# SDC_LATCH_LS.net
KiCad netlist of a schematic drawn in Altium Designer
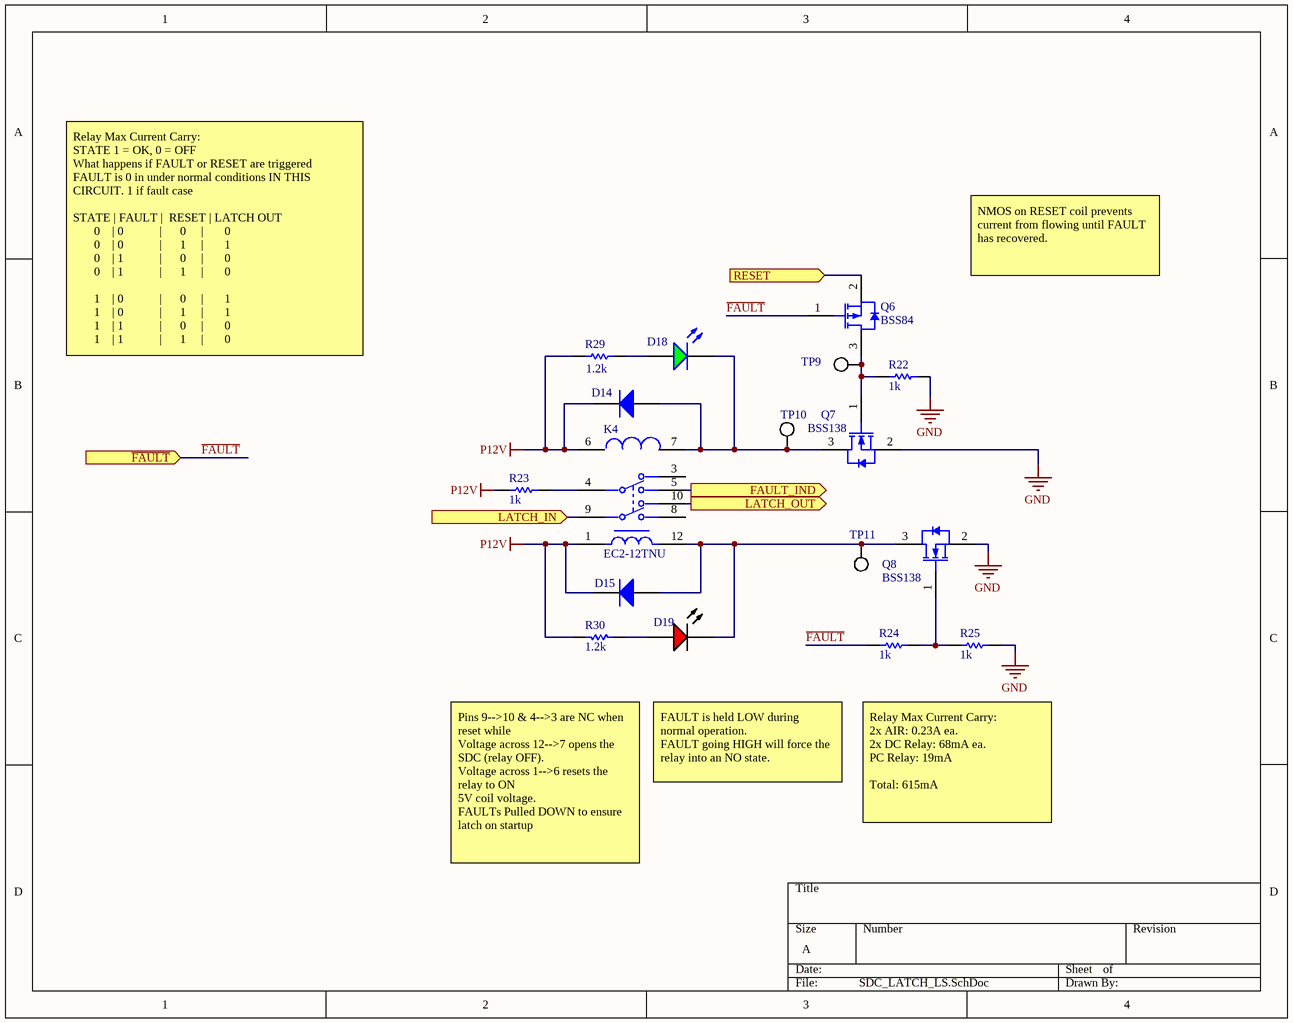
[diagram p0:  SDC_LATCH_LS.SchDoc]

(export (version "E")
  (design (tool "Eeschema 10.0.6"))
  (components
    (comp (ref "D14")
      (value "Diode 1N4148")
      (footprint "DO-35")
      (description "High Conductance Fast Diode")
      (fields (field (name "PUBLISHER") "Altium Limited"))
      (libsource (lib "Miscellaneous Devices") (part "Diode 1N4148"))
    )
    (comp (ref "D15")
      (value "Diode 1N4148")
      (footprint "DO-35")
      (description "High Conductance Fast Diode")
      (fields (field (name "PUBLISHER") "Altium Limited"))
      (libsource (lib "Miscellaneous Devices") (part "Diode 1N4148"))
    )
    (comp (ref "D18")
      (value "597-3311-407F")
      (footprint "DIAL-597-3311-407F_V")
      (description "LED Green, 75 mW, 30 mA, -30 to 85 degC, 2-Pin SMD, RoHS, Tape and Reel")
      (fields (field (name "MANUFACTURER") "Dialight"))
      (libsource (lib "Altium Content Vault") (part "LED-GREEN-AK-2"))
    )
    (comp (ref "D19")
      (value "SML-LX1206IC-TR")
      (footprint "LUMX-SML-LX1206IC_V")
      (description "LED Red, 65 mW, -40 to 85 degC, 2-Pin SMD, RoHS, Tape and Reel")
      (fields (field (name "MANUFACTURER") "Lumex"))
      (libsource (lib "Altium Content Vault") (part "LED-RED-AK-2"))
    )
    (comp (ref "K4")
      (value "EC2-12TNU")
      (footprint "FP-EC2-12TNU-MFG")
      (description "RELAY GEN PURPOSE DPDT 2A 12VDC")
      (fields
        (field (name "MANUFACTURER") "KEMET")
        (field (name "OCTOPART") "https://octopart.com/ec2-12tnu-kemet-30529205")
      )
      (libsource (lib "Altium Content Vault") (part "a00bcedd7ab582def7fa3ba9be5e2d2"))
    )
    (comp (ref "Q6")
      (value "BSS84")
      (footprint "FAIR-SOT23-3_V")
      (fields (field (name "MANUFACTURER") "Fairchild") (field (name "POWER") "360mW"))
      (libsource (lib "University of California Riverside - FSAE") (part "PEMOS-GSD-3"))
    )
    (comp (ref "Q7")
      (value "BSS138")
      (footprint "FAIR-SOT23-3_V")
      (fields (field (name "MANUFACTURER") "Fairchild") (field (name "POWER") "360mW"))
      (libsource (lib "University of California Riverside - FSAE") (part "NEMOS-GSD-3"))
    )
    (comp (ref "Q8")
      (value "BSS138")
      (footprint "FAIR-SOT23-3_V")
      (fields (field (name "MANUFACTURER") "Fairchild") (field (name "POWER") "360mW"))
      (libsource (lib "University of California Riverside - FSAE") (part "NEMOS-GSD-3"))
    )
    (comp (ref "R22")
      (value "1k")
      (footprint "RESC3116X70X50ML13T20")
      (description "Chip Resistor, 1 KOhm, +/- 1%, 0.25 W, -55 to 155 degC, 1206 (3216 Metric)")
      (fields (field (name "POWER") "250mW") (field (name "TOLERANCE") "1%"))
      (libsource (lib "University of California Riverside - FSAE") (part "RES-2"))
    )
    (comp (ref "R23")
      (value "1k")
      (footprint "RESC3116X70X50ML13T20")
      (description "Chip Resistor, 1 KOhm, +/- 1%, 0.25 W, -55 to 155 degC, 1206 (3216 Metric)")
      (fields (field (name "POWER") "250mW") (field (name "TOLERANCE") "1%"))
      (libsource (lib "University of California Riverside - FSAE") (part "RES-2"))
    )
    (comp (ref "R24")
      (value "1k")
      (footprint "RESC3116X70X50ML13T20")
      (description "Chip Resistor, 1 KOhm, +/- 1%, 0.25 W, -55 to 155 degC, 1206 (3216 Metric)")
      (fields (field (name "POWER") "250mW") (field (name "TOLERANCE") "1%"))
      (libsource (lib "University of California Riverside - FSAE") (part "RES-2"))
    )
    (comp (ref "R25")
      (value "1k")
      (footprint "RESC3116X70X50ML13T20")
      (description "Chip Resistor, 1 KOhm, +/- 1%, 0.25 W, -55 to 155 degC, 1206 (3216 Metric)")
      (fields (field (name "POWER") "250mW") (field (name "TOLERANCE") "1%"))
      (libsource (lib "University of California Riverside - FSAE") (part "RES-2"))
    )
    (comp (ref "R29")
      (value "1.2k")
      (footprint "RESC3216X70X50LL05T20")
      (description "ERJ8ENF1201V")
      (fields (field (name "MANUFACTURER") "Panasonic"))
      (libsource (lib "Altium Content Vault") (part "RES"))
    )
    (comp (ref "R30")
      (value "1.2k")
      (footprint "RESC3216X70X50LL05T20")
      (description "ERJ8ENF1201V")
      (fields (field (name "MANUFACTURER") "Panasonic"))
      (libsource (lib "Altium Content Vault") (part "RES"))
    )
    (comp (ref "TP9")
      (value "Misc-Generic-TP")
      (footprint "FOOTPRINT-GENERIC-TP-VIA-1MM")
      (libsource (lib "University of California Riverside - FSAE") (part "Misc-Generic-TP"))
    )
    (comp (ref "TP10")
      (value "Misc-Generic-TP")
      (footprint "FOOTPRINT-GENERIC-TP-VIA-1MM")
      (libsource (lib "University of California Riverside - FSAE") (part "Misc-Generic-TP"))
    )
    (comp (ref "TP11")
      (value "Misc-Generic-TP")
      (footprint "FOOTPRINT-GENERIC-TP-VIA-1MM")
      (libsource (lib "University of California Riverside - FSAE") (part "Misc-Generic-TP"))
    )
  )
  (nets
    (net (code "1") (name "/FAULT_IND") (class "Default")
      (node (ref "K4") (pin "5") (pinfunction "5_5") (pintype "passive"))
    )
    (net (code "2") (name "/LATCH_IN") (class "Default")
      (node (ref "K4") (pin "9") (pinfunction "9_9") (pintype "passive"))
    )
    (net (code "3") (name "/LATCH_OUT") (class "Default")
      (node (ref "K4") (pin "10") (pinfunction "10_10") (pintype "passive"))
    )
    (net (code "4") (name "/RESET") (class "Default")
      (node (ref "Q6") (pin "2") (pinfunction "SOURCE_2") (pintype "passive"))
    )
    (net (code "5") (name "/~{FAULT}") (class "Default")
      (node (ref "Q6") (pin "1") (pinfunction "GATE_1") (pintype "passive"))
      (node (ref "R24") (pin "2") (pinfunction "2_2") (pintype "passive"))
    )
    (net (code "6") (name "GND") (class "Default")
      (node (ref "Q7") (pin "2") (pinfunction "S_2") (pintype "passive"))
      (node (ref "Q8") (pin "2") (pinfunction "S_2") (pintype "passive"))
      (node (ref "R22") (pin "1") (pinfunction "1_1") (pintype "passive"))
      (node (ref "R25") (pin "1") (pinfunction "1_1") (pintype "passive"))
    )
    (net (code "7") (name "Net-(D14-A)") (class "Default")
      (node (ref "D14") (pin "1") (pinfunction "A_1") (pintype "passive"))
      (node (ref "D18") (pin "2") (pinfunction "K_2") (pintype "passive"))
      (node (ref "K4") (pin "7") (pinfunction "RESET-_7") (pintype "passive"))
      (node (ref "Q7") (pin "3") (pinfunction "D_3") (pintype "passive"))
      (node (ref "TP10") (pin "1") (pinfunction "TP_1") (pintype "passive"))
    )
    (net (code "8") (name "Net-(D15-A)") (class "Default")
      (node (ref "D15") (pin "1") (pinfunction "A_1") (pintype "passive"))
      (node (ref "D19") (pin "2") (pinfunction "K_2") (pintype "passive"))
      (node (ref "K4") (pin "12") (pinfunction "SET-_12") (pintype "passive"))
      (node (ref "Q8") (pin "3") (pinfunction "D_3") (pintype "passive"))
      (node (ref "TP11") (pin "1") (pinfunction "TP_1") (pintype "passive"))
    )
    (net (code "9") (name "Net-(D18-A)") (class "Default")
      (node (ref "D18") (pin "1") (pinfunction "A_1") (pintype "passive"))
      (node (ref "R29") (pin "2") (pinfunction "2_2") (pintype "passive"))
    )
    (net (code "10") (name "Net-(D19-A)") (class "Default")
      (node (ref "D19") (pin "1") (pinfunction "A_1") (pintype "passive"))
      (node (ref "R30") (pin "2") (pinfunction "2_2") (pintype "passive"))
    )
    (net (code "11") (name "Net-(K4-Pad4)") (class "Default")
      (node (ref "K4") (pin "4") (pinfunction "4_4") (pintype "passive"))
      (node (ref "R23") (pin "1") (pinfunction "1_1") (pintype "passive"))
    )
    (net (code "12") (name "Net-(Q6-DRAIN)") (class "Default")
      (node (ref "Q6") (pin "3") (pinfunction "DRAIN_3") (pintype "passive"))
      (node (ref "Q7") (pin "1") (pinfunction "G_1") (pintype "passive"))
      (node (ref "R22") (pin "2") (pinfunction "2_2") (pintype "passive"))
      (node (ref "TP9") (pin "1") (pinfunction "TP_1") (pintype "passive"))
    )
    (net (code "13") (name "Net-(Q8-G)") (class "Default")
      (node (ref "Q8") (pin "1") (pinfunction "G_1") (pintype "passive"))
      (node (ref "R24") (pin "1") (pinfunction "1_1") (pintype "passive"))
      (node (ref "R25") (pin "2") (pinfunction "2_2") (pintype "passive"))
    )
    (net (code "14") (name "P12V") (class "Default")
      (node (ref "D14") (pin "2") (pinfunction "K_2") (pintype "passive"))
      (node (ref "D15") (pin "2") (pinfunction "K_2") (pintype "passive"))
      (node (ref "K4") (pin "1") (pinfunction "SET+_1") (pintype "passive"))
      (node (ref "K4") (pin "6") (pinfunction "RESET+_6") (pintype "passive"))
      (node (ref "R23") (pin "2") (pinfunction "2_2") (pintype "passive"))
      (node (ref "R29") (pin "1") (pinfunction "1_1") (pintype "passive"))
      (node (ref "R30") (pin "1") (pinfunction "1_1") (pintype "passive"))
    )
    (net (code "15") (name "unconnected-(K4-Pad3)") (class "Default")
      (node (ref "K4") (pin "3") (pinfunction "3_3") (pintype "passive"))
    )
    (net (code "16") (name "unconnected-(K4-Pad8)") (class "Default")
      (node (ref "K4") (pin "8") (pinfunction "8_8") (pintype "passive"))
    )
  )
)
